# 3_3VDC_Powersupply.net
KiCad netlist of a schematic drawn in Altium Designer
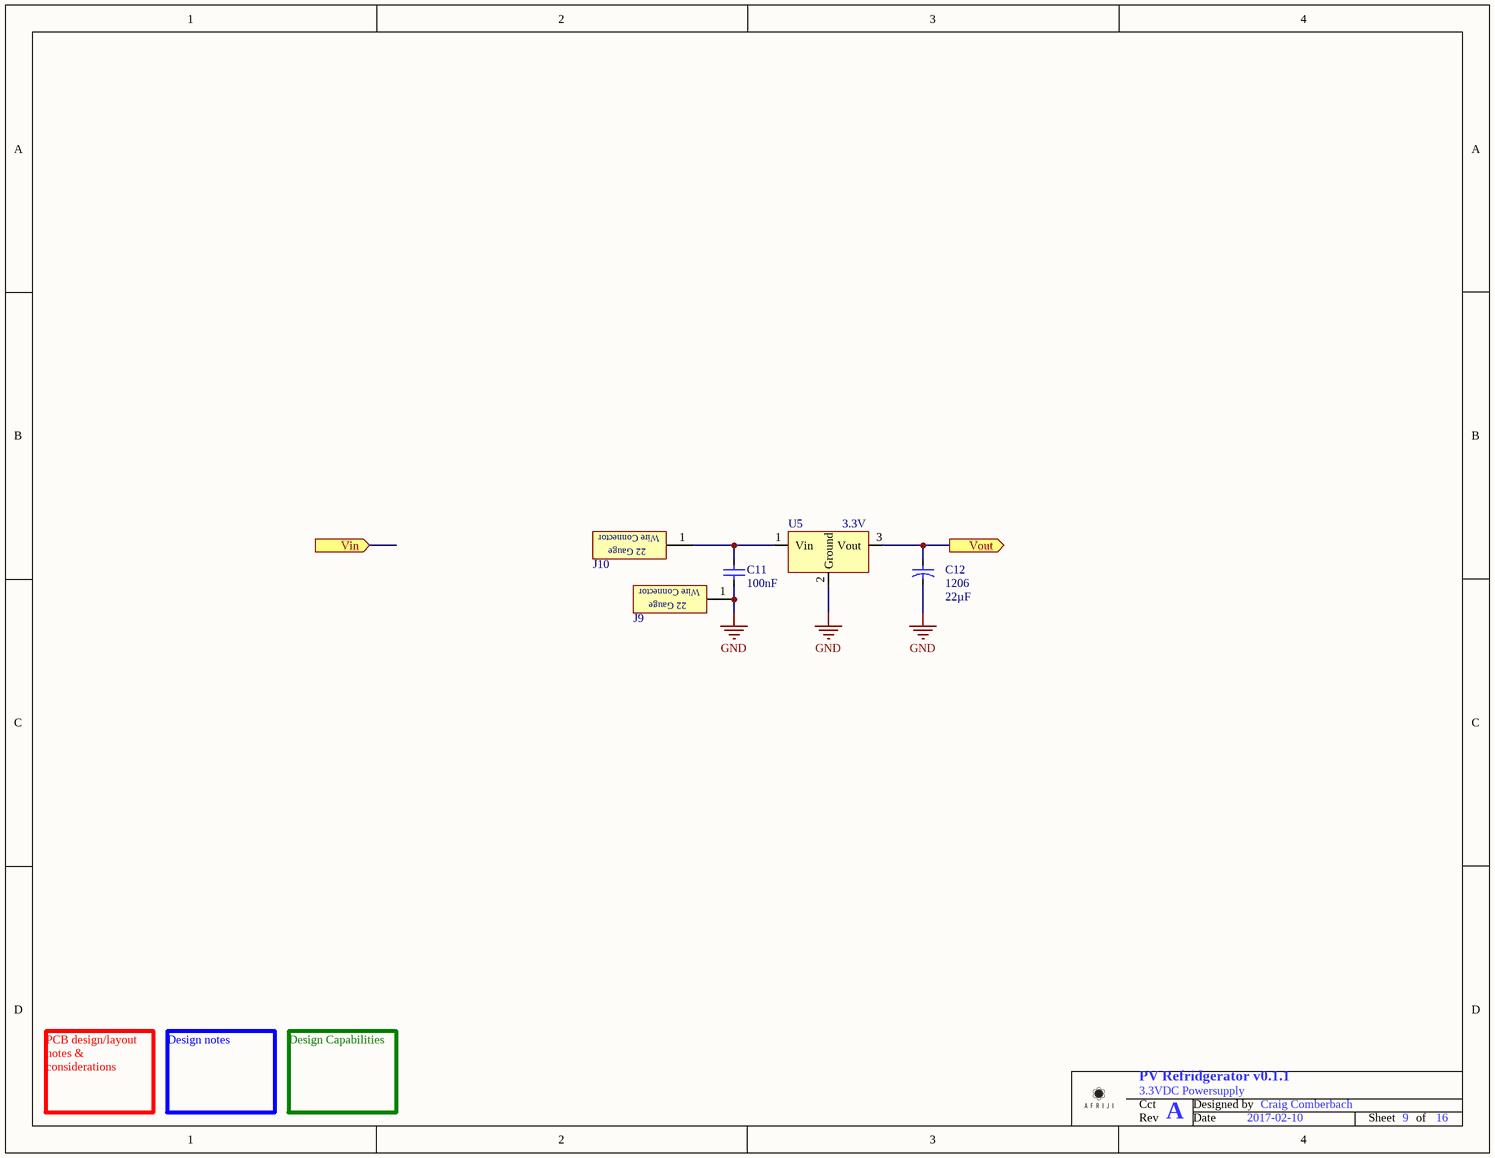
[diagram p0: 3.3VDC Powersupply.SchDoc]

(export (version "E")
  (design (tool "Eeschema 10.0.6"))
  (components
    (comp (ref "C11")
      (value "100nF 0603 50V")
      (footprint "Capacitor - 0603 Ceramic")
      (description "Non-polarized")
      (fields
        (field (name "MANUFACTURER") "Murata Electronics North America")
        (field (name "MANUFACTURER PART NUMBER") "GRM188R71H104KA93D")
        (field (name "CAPACITANCE") "100nF")
      )
      (libsource (lib "Integrated Component Library") (part "100nF 0603 50V"))
    )
    (comp (ref "C12")
      (value "1206")
      (footprint "Capacitor - 1210 Tantalum")
      (description "Polarized")
      (fields
        (field (name "MANUFACTURER") "AVX Corporation")
        (field (name "MANUFACTURER PART NUMBER") "TAJB226K010RNJ")
        (field (name "CAPACITANCE") "22µF")
      )
      (libsource (lib "Integrated Component Library") (part "22uF 1210 10V - Tantalum"))
    )
    (comp (ref "J9")
      (value "GND")
      (footprint "1 Pin 22-Gauge Wire Connector")
      (libsource (lib "Personal Library") (part "1 Pin 22-Gauge Wire connector"))
    )
    (comp (ref "J10")
      (value "3.3VDC")
      (footprint "1 Pin 22-Gauge Wire Connector")
      (libsource (lib "Personal Library") (part "1 Pin 22-Gauge Wire connector"))
    )
    (comp (ref "U5")
      (value "3.3V Linear Voltage Regulator LDO")
      (footprint "SOT223")
      (description "500mA")
      (fields
        (field (name "MANUFACTURER") "Micrel Inc")
        (field (name "MANUFACTURER PART NUMBER") "MIC5209-3.3YS TR")
        (field (name "VOLTAGE - OUTPUT") "3.3V")
      )
      (libsource (lib "Integrated Component Library") (part "3.3V Linear Voltage Regulator LDO"))
    )
  )
  (nets
    (net (code "2") (name "/Vout") (class "Default")
      (node (ref "C12") (pin "1") (pinfunction "1_1") (pintype "passive"))
      (node (ref "U5") (pin "3") (pinfunction "Vout_3") (pintype "passive"))
    )
    (net (code "3") (name "GND") (class "Default")
      (node (ref "C11") (pin "2") (pinfunction "2_2") (pintype "passive"))
      (node (ref "C12") (pin "2") (pinfunction "2_2") (pintype "passive"))
      (node (ref "J9") (pin "1") (pinfunction "1_1") (pintype "passive"))
      (node (ref "U5") (pin "2") (pinfunction "Ground_2") (pintype "passive"))
    )
    (net (code "4") (name "Net-(U5-Vin)") (class "Default")
      (node (ref "C11") (pin "1") (pinfunction "1_1") (pintype "passive"))
      (node (ref "J10") (pin "1") (pinfunction "1_1") (pintype "passive"))
      (node (ref "U5") (pin "1") (pinfunction "Vin_1") (pintype "passive"))
    )
  )
)
